# logic_board_Protorype_5_4_ver1.net
KiCad netlist of a schematic drawn in EAGLE
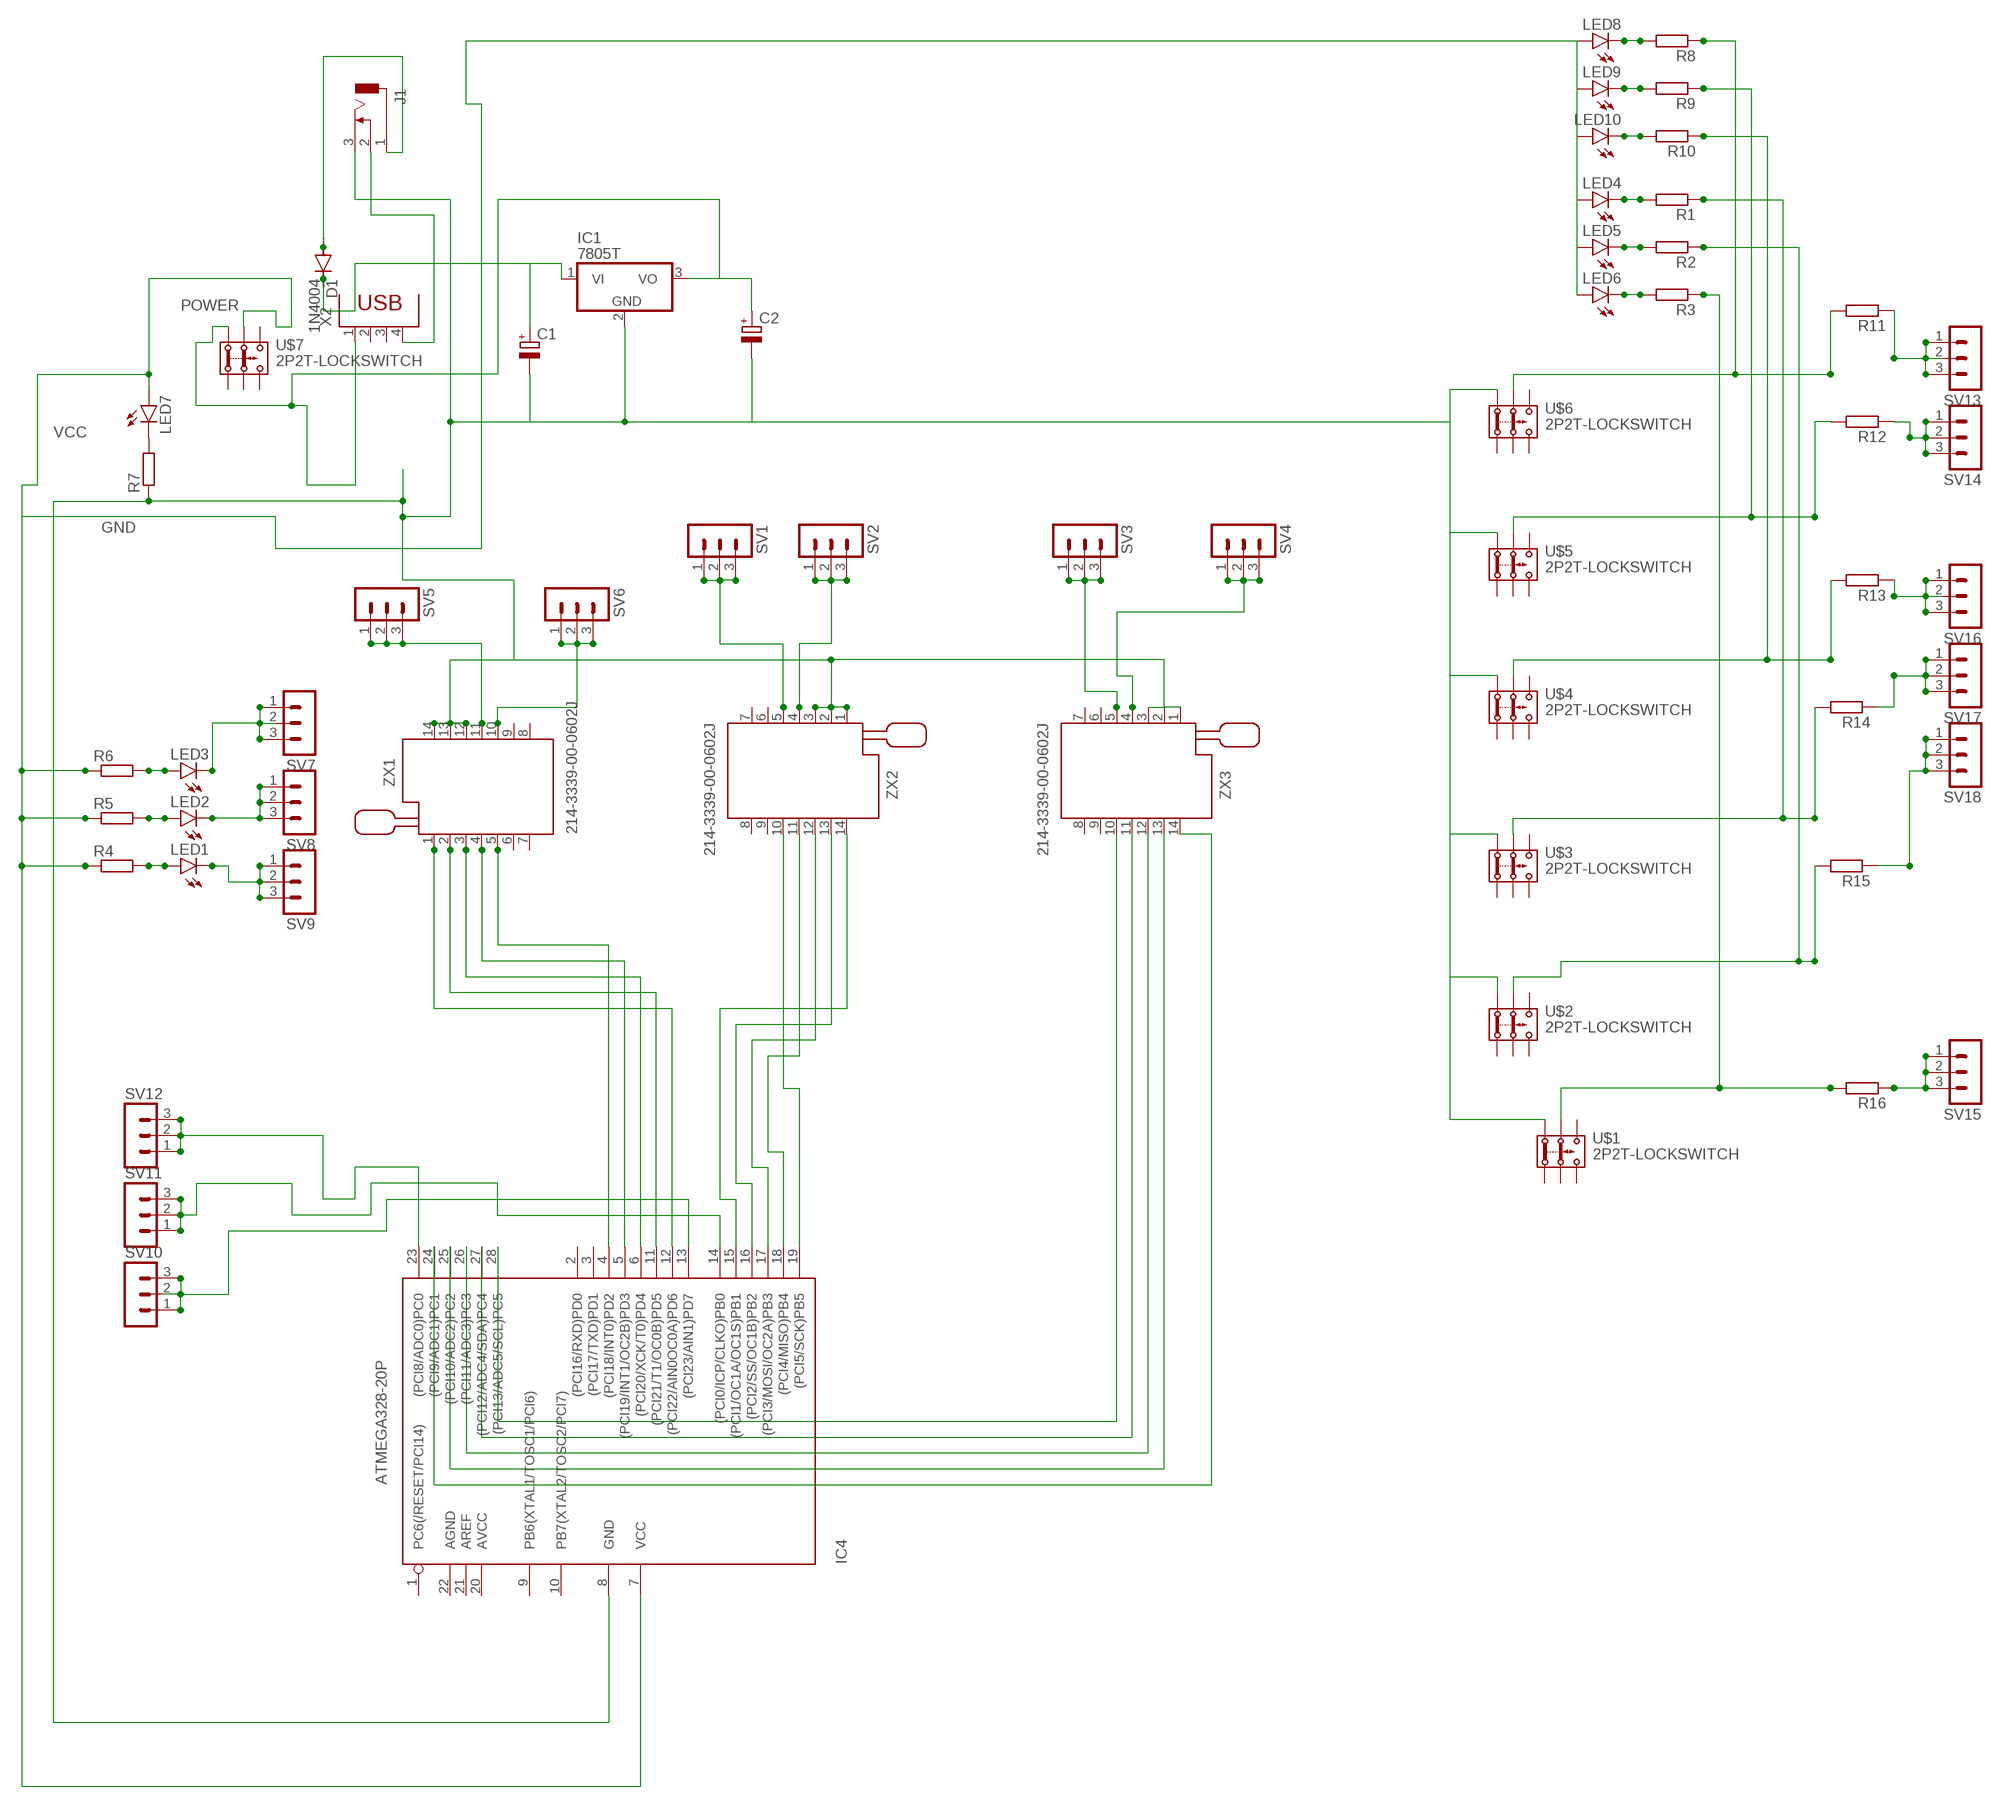
[diagram p0: schematic, sheet 1]

(export (version "E")
  (design (tool "Eeschema 10.0.6"))
  (components
    (comp (ref "C1")
      (value "CPOL-EUE2.5-6")
      (footprint "eagle-import:E2,5-6")
      (libsource (lib "eagle-import") (part "CPOL-EUE2.5-6"))
    )
    (comp (ref "C2")
      (value "CPOL-EUE2.5-6")
      (footprint "eagle-import:E2,5-6")
      (libsource (lib "eagle-import") (part "CPOL-EUE2.5-6"))
    )
    (comp (ref "D1")
      (value "1N4004")
      (footprint "eagle-import:DO41-10")
      (libsource (lib "eagle-import") (part "1N4004"))
    )
    (comp (ref "IC1")
      (value "7805T")
      (footprint "eagle-import:TO220H")
      (libsource (lib "eagle-import") (part "78T05"))
    )
    (comp (ref "IC4")
      (value "ATMEGA328-20P")
      (footprint "eagle-import:DIL28-3")
      (libsource (lib "eagle-import") (part "ATMEGA328P-20"))
    )
    (comp (ref "J1")
      (value "DCJ0303")
      (footprint "eagle-import:DCJ0303")
      (libsource (lib "eagle-import") (part "DCJ0303"))
    )
    (comp (ref "LED1")
      (value "LED5MM")
      (footprint "eagle-import:LED5MM")
      (libsource (lib "eagle-import") (part "LED5MM"))
    )
    (comp (ref "LED2")
      (value "LED5MM")
      (footprint "eagle-import:LED5MM")
      (libsource (lib "eagle-import") (part "LED5MM"))
    )
    (comp (ref "LED3")
      (value "LED5MM")
      (footprint "eagle-import:LED5MM")
      (libsource (lib "eagle-import") (part "LED5MM"))
    )
    (comp (ref "LED4")
      (value "LED5MM")
      (footprint "eagle-import:LED5MM")
      (libsource (lib "eagle-import") (part "LED5MM"))
    )
    (comp (ref "LED5")
      (value "LED5MM")
      (footprint "eagle-import:LED5MM")
      (libsource (lib "eagle-import") (part "LED5MM"))
    )
    (comp (ref "LED6")
      (value "LED5MM")
      (footprint "eagle-import:LED5MM")
      (libsource (lib "eagle-import") (part "LED5MM"))
    )
    (comp (ref "LED7")
      (value "LED5MM")
      (footprint "eagle-import:LED5MM")
      (libsource (lib "eagle-import") (part "LED5MM"))
    )
    (comp (ref "LED8")
      (value "LED5MM")
      (footprint "eagle-import:LED5MM")
      (libsource (lib "eagle-import") (part "LED5MM"))
    )
    (comp (ref "LED9")
      (value "LED5MM")
      (footprint "eagle-import:LED5MM")
      (libsource (lib "eagle-import") (part "LED5MM"))
    )
    (comp (ref "LED10")
      (value "LED5MM")
      (footprint "eagle-import:LED5MM")
      (libsource (lib "eagle-import") (part "LED5MM"))
    )
    (comp (ref "R1")
      (value "R-EU_0207/10")
      (footprint "eagle-import:0207_10")
      (libsource (lib "eagle-import") (part "R-EU_0207/10"))
    )
    (comp (ref "R2")
      (value "R-EU_0207/10")
      (footprint "eagle-import:0207_10")
      (libsource (lib "eagle-import") (part "R-EU_0207/10"))
    )
    (comp (ref "R3")
      (value "R-EU_0207/10")
      (footprint "eagle-import:0207_10")
      (libsource (lib "eagle-import") (part "R-EU_0207/10"))
    )
    (comp (ref "R4")
      (value "R-EU_0207/10")
      (footprint "eagle-import:0207_10")
      (libsource (lib "eagle-import") (part "R-EU_0207/10"))
    )
    (comp (ref "R5")
      (value "R-EU_0207/10")
      (footprint "eagle-import:0207_10")
      (libsource (lib "eagle-import") (part "R-EU_0207/10"))
    )
    (comp (ref "R6")
      (value "R-EU_0207/10")
      (footprint "eagle-import:0207_10")
      (libsource (lib "eagle-import") (part "R-EU_0207/10"))
    )
    (comp (ref "R7")
      (value "R-EU_0207/10")
      (footprint "eagle-import:0207_10")
      (libsource (lib "eagle-import") (part "R-EU_0207/10"))
    )
    (comp (ref "R8")
      (value "R-EU_0207/10")
      (footprint "eagle-import:0207_10")
      (libsource (lib "eagle-import") (part "R-EU_0207/10"))
    )
    (comp (ref "R9")
      (value "R-EU_0207/10")
      (footprint "eagle-import:0207_10")
      (libsource (lib "eagle-import") (part "R-EU_0207/10"))
    )
    (comp (ref "R10")
      (value "R-EU_0207/10")
      (footprint "eagle-import:0207_10")
      (libsource (lib "eagle-import") (part "R-EU_0207/10"))
    )
    (comp (ref "R11")
      (value "R-EU_0207/10")
      (footprint "eagle-import:0207_10")
      (libsource (lib "eagle-import") (part "R-EU_0207/10"))
    )
    (comp (ref "R12")
      (value "R-EU_0207/10")
      (footprint "eagle-import:0207_10")
      (libsource (lib "eagle-import") (part "R-EU_0207/10"))
    )
    (comp (ref "R13")
      (value "R-EU_0207/10")
      (footprint "eagle-import:0207_10")
      (libsource (lib "eagle-import") (part "R-EU_0207/10"))
    )
    (comp (ref "R14")
      (value "R-EU_0207/10")
      (footprint "eagle-import:0207_10")
      (libsource (lib "eagle-import") (part "R-EU_0207/10"))
    )
    (comp (ref "R15")
      (value "R-EU_0207/10")
      (footprint "eagle-import:0207_10")
      (libsource (lib "eagle-import") (part "R-EU_0207/10"))
    )
    (comp (ref "R16")
      (value "R-EU_0207/10")
      (footprint "eagle-import:0207_10")
      (libsource (lib "eagle-import") (part "R-EU_0207/10"))
    )
    (comp (ref "SV1")
      (value "MA03-1")
      (footprint "eagle-import:MA03-1")
      (libsource (lib "eagle-import") (part "MA03-1"))
    )
    (comp (ref "SV2")
      (value "MA03-1")
      (footprint "eagle-import:MA03-1")
      (libsource (lib "eagle-import") (part "MA03-1"))
    )
    (comp (ref "SV3")
      (value "MA03-1")
      (footprint "eagle-import:MA03-1")
      (libsource (lib "eagle-import") (part "MA03-1"))
    )
    (comp (ref "SV4")
      (value "MA03-1")
      (footprint "eagle-import:MA03-1")
      (libsource (lib "eagle-import") (part "MA03-1"))
    )
    (comp (ref "SV5")
      (value "MA03-1")
      (footprint "eagle-import:MA03-1")
      (libsource (lib "eagle-import") (part "MA03-1"))
    )
    (comp (ref "SV6")
      (value "MA03-1")
      (footprint "eagle-import:MA03-1")
      (libsource (lib "eagle-import") (part "MA03-1"))
    )
    (comp (ref "SV7")
      (value "MA03-1")
      (footprint "eagle-import:MA03-1")
      (libsource (lib "eagle-import") (part "MA03-1"))
    )
    (comp (ref "SV8")
      (value "MA03-1")
      (footprint "eagle-import:MA03-1")
      (libsource (lib "eagle-import") (part "MA03-1"))
    )
    (comp (ref "SV9")
      (value "MA03-1")
      (footprint "eagle-import:MA03-1")
      (libsource (lib "eagle-import") (part "MA03-1"))
    )
    (comp (ref "SV10")
      (value "MA03-1")
      (footprint "eagle-import:MA03-1")
      (libsource (lib "eagle-import") (part "MA03-1"))
    )
    (comp (ref "SV11")
      (value "MA03-1")
      (footprint "eagle-import:MA03-1")
      (libsource (lib "eagle-import") (part "MA03-1"))
    )
    (comp (ref "SV12")
      (value "MA03-1")
      (footprint "eagle-import:MA03-1")
      (libsource (lib "eagle-import") (part "MA03-1"))
    )
    (comp (ref "SV13")
      (value "MA03-1")
      (footprint "eagle-import:MA03-1")
      (libsource (lib "eagle-import") (part "MA03-1"))
    )
    (comp (ref "SV14")
      (value "MA03-1")
      (footprint "eagle-import:MA03-1")
      (libsource (lib "eagle-import") (part "MA03-1"))
    )
    (comp (ref "SV15")
      (value "MA03-1")
      (footprint "eagle-import:MA03-1")
      (libsource (lib "eagle-import") (part "MA03-1"))
    )
    (comp (ref "SV16")
      (value "MA03-1")
      (footprint "eagle-import:MA03-1")
      (libsource (lib "eagle-import") (part "MA03-1"))
    )
    (comp (ref "SV17")
      (value "MA03-1")
      (footprint "eagle-import:MA03-1")
      (libsource (lib "eagle-import") (part "MA03-1"))
    )
    (comp (ref "SV18")
      (value "MA03-1")
      (footprint "eagle-import:MA03-1")
      (libsource (lib "eagle-import") (part "MA03-1"))
    )
    (comp (ref "U$1")
      (value "2P2T-LOCKSWITCH")
      (footprint "eagle-import:2P2T-LOCKSWITCH")
      (libsource (lib "eagle-import") (part "2P2T-LOCKSWITCH"))
    )
    (comp (ref "U$2")
      (value "2P2T-LOCKSWITCH")
      (footprint "eagle-import:2P2T-LOCKSWITCH")
      (libsource (lib "eagle-import") (part "2P2T-LOCKSWITCH"))
    )
    (comp (ref "U$3")
      (value "2P2T-LOCKSWITCH")
      (footprint "eagle-import:2P2T-LOCKSWITCH")
      (libsource (lib "eagle-import") (part "2P2T-LOCKSWITCH"))
    )
    (comp (ref "U$4")
      (value "2P2T-LOCKSWITCH")
      (footprint "eagle-import:2P2T-LOCKSWITCH")
      (libsource (lib "eagle-import") (part "2P2T-LOCKSWITCH"))
    )
    (comp (ref "U$5")
      (value "2P2T-LOCKSWITCH")
      (footprint "eagle-import:2P2T-LOCKSWITCH")
      (libsource (lib "eagle-import") (part "2P2T-LOCKSWITCH"))
    )
    (comp (ref "U$6")
      (value "2P2T-LOCKSWITCH")
      (footprint "eagle-import:2P2T-LOCKSWITCH")
      (libsource (lib "eagle-import") (part "2P2T-LOCKSWITCH"))
    )
    (comp (ref "U$7")
      (value "2P2T-LOCKSWITCH")
      (footprint "eagle-import:2P2T-LOCKSWITCH")
      (libsource (lib "eagle-import") (part "2P2T-LOCKSWITCH"))
    )
    (comp (ref "X2")
      (value "PN61729")
      (footprint "eagle-import:PN61729")
      (libsource (lib "eagle-import") (part "PN61729"))
    )
    (comp (ref "ZX1")
      (value "214-3339-00-0602J")
      (footprint "eagle-import:214-3339-00-0602J")
      (fields (field (name "MF") "3M"))
      (libsource (lib "eagle-import") (part "214-3339-00-0602J"))
    )
    (comp (ref "ZX2")
      (value "214-3339-00-0602J")
      (footprint "eagle-import:214-3339-00-0602J")
      (fields (field (name "MF") "3M"))
      (libsource (lib "eagle-import") (part "214-3339-00-0602J"))
    )
    (comp (ref "ZX3")
      (value "214-3339-00-0602J")
      (footprint "eagle-import:214-3339-00-0602J")
      (fields (field (name "MF") "3M"))
      (libsource (lib "eagle-import") (part "214-3339-00-0602J"))
    )
  )
  (nets
    (net (code "1") (name "/GND") (class "Default")
      (node (ref "C1") (pin "-") (pinfunction "-_-") (pintype "passive"))
      (node (ref "C2") (pin "-") (pinfunction "-_-") (pintype "passive"))
      (node (ref "IC1") (pin "2") (pinfunction "GND_2") (pintype "passive"))
      (node (ref "IC4") (pin "8") (pinfunction "GND_8") (pintype "bidirectional"))
      (node (ref "J1") (pin "3") (pinfunction "3_3") (pintype "passive"))
      (node (ref "R7") (pin "1") (pinfunction "1_1") (pintype "passive"))
      (node (ref "U$1") (pin "1.1") (pinfunction "1.1_1.1") (pintype "passive"))
      (node (ref "U$2") (pin "1.1") (pinfunction "1.1_1.1") (pintype "passive"))
      (node (ref "U$3") (pin "1.1") (pinfunction "1.1_1.1") (pintype "passive"))
      (node (ref "U$4") (pin "1.1") (pinfunction "1.1_1.1") (pintype "passive"))
      (node (ref "U$5") (pin "1.1") (pinfunction "1.1_1.1") (pintype "passive"))
      (node (ref "U$6") (pin "1.1") (pinfunction "1.1_1.1") (pintype "passive"))
      (node (ref "ZX1") (pin "12") (pinfunction "12_12") (pintype "passive"))
      (node (ref "ZX1") (pin "13") (pinfunction "13_13") (pintype "passive"))
      (node (ref "ZX1") (pin "14") (pinfunction "14_14") (pintype "passive"))
      (node (ref "ZX2") (pin "1") (pinfunction "1_1") (pintype "passive"))
      (node (ref "ZX2") (pin "2") (pinfunction "2_2") (pintype "passive"))
      (node (ref "ZX2") (pin "3") (pinfunction "3_3") (pintype "passive"))
      (node (ref "ZX3") (pin "1") (pinfunction "1_1") (pintype "passive"))
      (node (ref "ZX3") (pin "2") (pinfunction "2_2") (pintype "passive"))
      (node (ref "ZX3") (pin "3") (pinfunction "3_3") (pintype "passive"))
    )
    (net (code "2") (name "/POWER") (class "Default")
      (node (ref "C2") (pin "+") (pinfunction "+_+") (pintype "passive"))
      (node (ref "IC1") (pin "3") (pinfunction "VO_3") (pintype "passive"))
      (node (ref "U$7") (pin "1.1") (pinfunction "1.1_1.1") (pintype "passive"))
      (node (ref "X2") (pin "1") (pinfunction "1_1") (pintype "passive"))
    )
    (net (code "3") (name "/VCC") (class "Default")
      (node (ref "IC4") (pin "7") (pinfunction "VCC_7") (pintype "bidirectional"))
      (node (ref "LED10") (pin "A") (pinfunction "A_A") (pintype "passive"))
      (node (ref "LED4") (pin "A") (pinfunction "A_A") (pintype "passive"))
      (node (ref "LED5") (pin "A") (pinfunction "A_A") (pintype "passive"))
      (node (ref "LED6") (pin "A") (pinfunction "A_A") (pintype "passive"))
      (node (ref "LED7") (pin "A") (pinfunction "A_A") (pintype "passive"))
      (node (ref "LED8") (pin "A") (pinfunction "A_A") (pintype "passive"))
      (node (ref "LED9") (pin "A") (pinfunction "A_A") (pintype "passive"))
      (node (ref "R4") (pin "1") (pinfunction "1_1") (pintype "passive"))
      (node (ref "R5") (pin "1") (pinfunction "1_1") (pintype "passive"))
      (node (ref "R6") (pin "1") (pinfunction "1_1") (pintype "passive"))
      (node (ref "U$7") (pin "2.1") (pinfunction "2.1_2.1") (pintype "passive"))
    )
    (net (code "4") (name "Net-(D1-PadA)") (class "Default")
      (node (ref "D1") (pin "A") (pinfunction "A_A") (pintype "passive"))
      (node (ref "J1") (pin "1") (pinfunction "1_1") (pintype "passive"))
    )
    (net (code "5") (name "Net-(IC1-VI)") (class "Default")
      (node (ref "C1") (pin "+") (pinfunction "+_+") (pintype "passive"))
      (node (ref "D1") (pin "C") (pinfunction "C_C") (pintype "passive"))
      (node (ref "IC1") (pin "1") (pinfunction "VI_1") (pintype "input"))
    )
    (net (code "6") (name "Net-(IC4-(PCI0{slash}ICP{slash}CLKO)PB0)") (class "Default")
      (node (ref "IC4") (pin "14") (pinfunction "(PCI0/ICP/CLKO)PB0_14") (pintype "bidirectional"))
      (node (ref "SV11") (pin "1") (pinfunction "1_1") (pintype "passive"))
      (node (ref "SV11") (pin "2") (pinfunction "2_2") (pintype "passive"))
      (node (ref "SV11") (pin "3") (pinfunction "3_3") (pintype "passive"))
    )
    (net (code "7") (name "Net-(IC4-(PCI1{slash}OC1A{slash}OC1S)PB1)") (class "Default")
      (node (ref "IC4") (pin "15") (pinfunction "(PCI1/OC1A/OC1S)PB1_15") (pintype "bidirectional"))
      (node (ref "ZX2") (pin "14") (pinfunction "14_14") (pintype "passive"))
    )
    (net (code "8") (name "Net-(IC4-(PCI2{slash}SS{slash}OC1B)PB2)") (class "Default")
      (node (ref "IC4") (pin "16") (pinfunction "(PCI2/SS/OC1B)PB2_16") (pintype "bidirectional"))
      (node (ref "ZX2") (pin "13") (pinfunction "13_13") (pintype "passive"))
    )
    (net (code "9") (name "Net-(IC4-(PCI3{slash}MOSI{slash}OC2A)PB3)") (class "Default")
      (node (ref "IC4") (pin "17") (pinfunction "(PCI3/MOSI/OC2A)PB3_17") (pintype "bidirectional"))
      (node (ref "ZX2") (pin "12") (pinfunction "12_12") (pintype "passive"))
    )
    (net (code "10") (name "Net-(IC4-(PCI4{slash}MISO)PB4)") (class "Default")
      (node (ref "IC4") (pin "18") (pinfunction "(PCI4/MISO)PB4_18") (pintype "bidirectional"))
      (node (ref "ZX2") (pin "11") (pinfunction "11_11") (pintype "passive"))
    )
    (net (code "11") (name "Net-(IC4-(PCI5{slash}SCK)PB5)") (class "Default")
      (node (ref "IC4") (pin "19") (pinfunction "(PCI5/SCK)PB5_19") (pintype "bidirectional"))
      (node (ref "ZX2") (pin "10") (pinfunction "10_10") (pintype "passive"))
    )
    (net (code "12") (name "Net-(IC4-(PCI8{slash}ADC0)PC0)") (class "Default")
      (node (ref "IC4") (pin "23") (pinfunction "(PCI8/ADC0)PC0_23") (pintype "bidirectional"))
      (node (ref "SV12") (pin "1") (pinfunction "1_1") (pintype "passive"))
      (node (ref "SV12") (pin "2") (pinfunction "2_2") (pintype "passive"))
      (node (ref "SV12") (pin "3") (pinfunction "3_3") (pintype "passive"))
    )
    (net (code "13") (name "Net-(IC4-(PCI9{slash}ADC1)PC1)") (class "Default")
      (node (ref "IC4") (pin "24") (pinfunction "(PCI9/ADC1)PC1_24") (pintype "bidirectional"))
      (node (ref "ZX3") (pin "14") (pinfunction "14_14") (pintype "passive"))
    )
    (net (code "14") (name "Net-(IC4-(PCI10{slash}ADC2)PC2)") (class "Default")
      (node (ref "IC4") (pin "25") (pinfunction "(PCI10/ADC2)PC2_25") (pintype "bidirectional"))
      (node (ref "ZX3") (pin "13") (pinfunction "13_13") (pintype "passive"))
    )
    (net (code "15") (name "Net-(IC4-(PCI11{slash}ADC3)PC3)") (class "Default")
      (node (ref "IC4") (pin "26") (pinfunction "(PCI11/ADC3)PC3_26") (pintype "bidirectional"))
      (node (ref "ZX3") (pin "12") (pinfunction "12_12") (pintype "passive"))
    )
    (net (code "16") (name "Net-(IC4-(PCI12{slash}ADC4{slash}SDA)PC4)") (class "Default")
      (node (ref "IC4") (pin "27") (pinfunction "(PCI12/ADC4/SDA)PC4_27") (pintype "bidirectional"))
      (node (ref "ZX3") (pin "11") (pinfunction "11_11") (pintype "passive"))
    )
    (net (code "17") (name "Net-(IC4-(PCI13{slash}ADC5{slash}SCL)PC5)") (class "Default")
      (node (ref "IC4") (pin "28") (pinfunction "(PCI13/ADC5/SCL)PC5_28") (pintype "bidirectional"))
      (node (ref "ZX3") (pin "10") (pinfunction "10_10") (pintype "passive"))
    )
    (net (code "18") (name "Net-(IC4-(PCI18{slash}INT0)PD2)") (class "Default")
      (node (ref "IC4") (pin "4") (pinfunction "(PCI18/INT0)PD2_4") (pintype "bidirectional"))
      (node (ref "ZX1") (pin "5") (pinfunction "5_5") (pintype "passive"))
    )
    (net (code "19") (name "Net-(IC4-(PCI19{slash}INT1{slash}OC2B)PD3)") (class "Default")
      (node (ref "IC4") (pin "5") (pinfunction "(PCI19/INT1/OC2B)PD3_5") (pintype "bidirectional"))
      (node (ref "ZX1") (pin "4") (pinfunction "4_4") (pintype "passive"))
    )
    (net (code "20") (name "Net-(IC4-(PCI20{slash}XCK{slash}T0)PD4)") (class "Default")
      (node (ref "IC4") (pin "6") (pinfunction "(PCI20/XCK/T0)PD4_6") (pintype "bidirectional"))
      (node (ref "ZX1") (pin "3") (pinfunction "3_3") (pintype "passive"))
    )
    (net (code "21") (name "Net-(IC4-(PCI21{slash}T1{slash}OC0B)PD5)") (class "Default")
      (node (ref "IC4") (pin "11") (pinfunction "(PCI21/T1/OC0B)PD5_11") (pintype "bidirectional"))
      (node (ref "ZX1") (pin "2") (pinfunction "2_2") (pintype "passive"))
    )
    (net (code "22") (name "Net-(IC4-(PCI22{slash}AIN0OC0A)PD6)") (class "Default")
      (node (ref "IC4") (pin "12") (pinfunction "(PCI22/AIN0OC0A)PD6_12") (pintype "bidirectional"))
      (node (ref "ZX1") (pin "1") (pinfunction "1_1") (pintype "passive"))
    )
    (net (code "23") (name "Net-(IC4-(PCI23{slash}AIN1)PD7)") (class "Default")
      (node (ref "IC4") (pin "13") (pinfunction "(PCI23/AIN1)PD7_13") (pintype "bidirectional"))
      (node (ref "SV10") (pin "1") (pinfunction "1_1") (pintype "passive"))
      (node (ref "SV10") (pin "2") (pinfunction "2_2") (pintype "passive"))
      (node (ref "SV10") (pin "3") (pinfunction "3_3") (pintype "passive"))
    )
    (net (code "24") (name "Net-(J1-Pad2)") (class "Default")
      (node (ref "J1") (pin "2") (pinfunction "2_2") (pintype "passive"))
      (node (ref "X2") (pin "4") (pinfunction "4_4") (pintype "passive"))
    )
    (net (code "25") (name "Net-(LED1-C)") (class "Default")
      (node (ref "LED1") (pin "K") (pinfunction "C_K") (pintype "passive"))
      (node (ref "SV9") (pin "1") (pinfunction "1_1") (pintype "passive"))
      (node (ref "SV9") (pin "2") (pinfunction "2_2") (pintype "passive"))
      (node (ref "SV9") (pin "3") (pinfunction "3_3") (pintype "passive"))
    )
    (net (code "26") (name "Net-(LED1-PadA)") (class "Default")
      (node (ref "LED1") (pin "A") (pinfunction "A_A") (pintype "passive"))
      (node (ref "R4") (pin "2") (pinfunction "2_2") (pintype "passive"))
    )
    (net (code "27") (name "Net-(LED2-C)") (class "Default")
      (node (ref "LED2") (pin "K") (pinfunction "C_K") (pintype "passive"))
      (node (ref "SV8") (pin "1") (pinfunction "1_1") (pintype "passive"))
      (node (ref "SV8") (pin "2") (pinfunction "2_2") (pintype "passive"))
      (node (ref "SV8") (pin "3") (pinfunction "3_3") (pintype "passive"))
    )
    (net (code "28") (name "Net-(LED2-PadA)") (class "Default")
      (node (ref "LED2") (pin "A") (pinfunction "A_A") (pintype "passive"))
      (node (ref "R5") (pin "2") (pinfunction "2_2") (pintype "passive"))
    )
    (net (code "29") (name "Net-(LED3-C)") (class "Default")
      (node (ref "LED3") (pin "K") (pinfunction "C_K") (pintype "passive"))
      (node (ref "SV7") (pin "1") (pinfunction "1_1") (pintype "passive"))
      (node (ref "SV7") (pin "2") (pinfunction "2_2") (pintype "passive"))
      (node (ref "SV7") (pin "3") (pinfunction "3_3") (pintype "passive"))
    )
    (net (code "30") (name "Net-(LED3-PadA)") (class "Default")
      (node (ref "LED3") (pin "A") (pinfunction "A_A") (pintype "passive"))
      (node (ref "R6") (pin "2") (pinfunction "2_2") (pintype "passive"))
    )
    (net (code "31") (name "Net-(LED4-C)") (class "Default")
      (node (ref "LED4") (pin "K") (pinfunction "C_K") (pintype "passive"))
      (node (ref "R1") (pin "2") (pinfunction "2_2") (pintype "passive"))
    )
    (net (code "32") (name "Net-(LED5-C)") (class "Default")
      (node (ref "LED5") (pin "K") (pinfunction "C_K") (pintype "passive"))
      (node (ref "R2") (pin "2") (pinfunction "2_2") (pintype "passive"))
    )
    (net (code "33") (name "Net-(LED6-C)") (class "Default")
      (node (ref "LED6") (pin "K") (pinfunction "C_K") (pintype "passive"))
      (node (ref "R3") (pin "2") (pinfunction "2_2") (pintype "passive"))
    )
    (net (code "34") (name "Net-(LED7-C)") (class "Default")
      (node (ref "LED7") (pin "K") (pinfunction "C_K") (pintype "passive"))
      (node (ref "R7") (pin "2") (pinfunction "2_2") (pintype "passive"))
    )
    (net (code "35") (name "Net-(LED8-C)") (class "Default")
      (node (ref "LED8") (pin "K") (pinfunction "C_K") (pintype "passive"))
      (node (ref "R8") (pin "2") (pinfunction "2_2") (pintype "passive"))
    )
    (net (code "36") (name "Net-(LED9-C)") (class "Default")
      (node (ref "LED9") (pin "K") (pinfunction "C_K") (pintype "passive"))
      (node (ref "R9") (pin "2") (pinfunction "2_2") (pintype "passive"))
    )
    (net (code "37") (name "Net-(LED10-C)") (class "Default")
      (node (ref "LED10") (pin "K") (pinfunction "C_K") (pintype "passive"))
      (node (ref "R10") (pin "2") (pinfunction "2_2") (pintype "passive"))
    )
    (net (code "38") (name "Net-(R1-Pad1)") (class "Default")
      (node (ref "R1") (pin "1") (pinfunction "1_1") (pintype "passive"))
      (node (ref "R14") (pin "2") (pinfunction "2_2") (pintype "passive"))
      (node (ref "U$3") (pin "2.1") (pinfunction "2.1_2.1") (pintype "passive"))
    )
    (net (code "39") (name "Net-(R10-Pad1)") (class "Default")
      (node (ref "R10") (pin "1") (pinfunction "1_1") (pintype "passive"))
      (node (ref "R13") (pin "2") (pinfunction "2_2") (pintype "passive"))
      (node (ref "U$4") (pin "2.1") (pinfunction "2.1_2.1") (pintype "passive"))
    )
    (net (code "40") (name "Net-(R11-Pad1)") (class "Default")
      (node (ref "R11") (pin "1") (pinfunction "1_1") (pintype "passive"))
      (node (ref "SV13") (pin "1") (pinfunction "1_1") (pintype "passive"))
      (node (ref "SV13") (pin "2") (pinfunction "2_2") (pintype "passive"))
      (node (ref "SV13") (pin "3") (pinfunction "3_3") (pintype "passive"))
    )
    (net (code "41") (name "Net-(R11-Pad2)") (class "Default")
      (node (ref "R11") (pin "2") (pinfunction "2_2") (pintype "passive"))
      (node (ref "R8") (pin "1") (pinfunction "1_1") (pintype "passive"))
      (node (ref "U$6") (pin "2.1") (pinfunction "2.1_2.1") (pintype "passive"))
    )
    (net (code "42") (name "Net-(R12-Pad1)") (class "Default")
      (node (ref "R12") (pin "1") (pinfunction "1_1") (pintype "passive"))
      (node (ref "SV14") (pin "1") (pinfunction "1_1") (pintype "passive"))
      (node (ref "SV14") (pin "2") (pinfunction "2_2") (pintype "passive"))
      (node (ref "SV14") (pin "3") (pinfunction "3_3") (pintype "passive"))
    )
    (net (code "43") (name "Net-(R12-Pad2)") (class "Default")
      (node (ref "R12") (pin "2") (pinfunction "2_2") (pintype "passive"))
      (node (ref "R9") (pin "1") (pinfunction "1_1") (pintype "passive"))
      (node (ref "U$5") (pin "2.1") (pinfunction "2.1_2.1") (pintype "passive"))
    )
    (net (code "44") (name "Net-(R13-Pad1)") (class "Default")
      (node (ref "R13") (pin "1") (pinfunction "1_1") (pintype "passive"))
      (node (ref "SV16") (pin "1") (pinfunction "1_1") (pintype "passive"))
      (node (ref "SV16") (pin "2") (pinfunction "2_2") (pintype "passive"))
      (node (ref "SV16") (pin "3") (pinfunction "3_3") (pintype "passive"))
    )
    (net (code "45") (name "Net-(R14-Pad1)") (class "Default")
      (node (ref "R14") (pin "1") (pinfunction "1_1") (pintype "passive"))
      (node (ref "SV17") (pin "1") (pinfunction "1_1") (pintype "passive"))
      (node (ref "SV17") (pin "2") (pinfunction "2_2") (pintype "passive"))
      (node (ref "SV17") (pin "3") (pinfunction "3_3") (pintype "passive"))
    )
    (net (code "46") (name "Net-(R15-Pad1)") (class "Default")
      (node (ref "R15") (pin "1") (pinfunction "1_1") (pintype "passive"))
      (node (ref "SV18") (pin "1") (pinfunction "1_1") (pintype "passive"))
      (node (ref "SV18") (pin "2") (pinfunction "2_2") (pintype "passive"))
      (node (ref "SV18") (pin "3") (pinfunction "3_3") (pintype "passive"))
    )
    (net (code "47") (name "Net-(R15-Pad2)") (class "Default")
      (node (ref "R15") (pin "2") (pinfunction "2_2") (pintype "passive"))
      (node (ref "R2") (pin "1") (pinfunction "1_1") (pintype "passive"))
      (node (ref "U$2") (pin "2.1") (pinfunction "2.1_2.1") (pintype "passive"))
    )
    (net (code "48") (name "Net-(R16-Pad1)") (class "Default")
      (node (ref "R16") (pin "1") (pinfunction "1_1") (pintype "passive"))
      (node (ref "SV15") (pin "1") (pinfunction "1_1") (pintype "passive"))
      (node (ref "SV15") (pin "2") (pinfunction "2_2") (pintype "passive"))
      (node (ref "SV15") (pin "3") (pinfunction "3_3") (pintype "passive"))
    )
    (net (code "49") (name "Net-(R16-Pad2)") (class "Default")
      (node (ref "R16") (pin "2") (pinfunction "2_2") (pintype "passive"))
      (node (ref "R3") (pin "1") (pinfunction "1_1") (pintype "passive"))
      (node (ref "U$1") (pin "2.1") (pinfunction "2.1_2.1") (pintype "passive"))
    )
    (net (code "50") (name "Net-(SV1-Pad1)") (class "Default")
      (node (ref "SV1") (pin "1") (pinfunction "1_1") (pintype "passive"))
      (node (ref "SV1") (pin "2") (pinfunction "2_2") (pintype "passive"))
      (node (ref "SV1") (pin "3") (pinfunction "3_3") (pintype "passive"))
      (node (ref "ZX2") (pin "5") (pinfunction "5_5") (pintype "passive"))
    )
    (net (code "51") (name "Net-(SV2-Pad1)") (class "Default")
      (node (ref "SV2") (pin "1") (pinfunction "1_1") (pintype "passive"))
      (node (ref "SV2") (pin "2") (pinfunction "2_2") (pintype "passive"))
      (node (ref "SV2") (pin "3") (pinfunction "3_3") (pintype "passive"))
      (node (ref "ZX2") (pin "4") (pinfunction "4_4") (pintype "passive"))
    )
    (net (code "52") (name "Net-(SV3-Pad1)") (class "Default")
      (node (ref "SV3") (pin "1") (pinfunction "1_1") (pintype "passive"))
      (node (ref "SV3") (pin "2") (pinfunction "2_2") (pintype "passive"))
      (node (ref "SV3") (pin "3") (pinfunction "3_3") (pintype "passive"))
      (node (ref "ZX3") (pin "5") (pinfunction "5_5") (pintype "passive"))
    )
    (net (code "53") (name "Net-(SV4-Pad1)") (class "Default")
      (node (ref "SV4") (pin "1") (pinfunction "1_1") (pintype "passive"))
      (node (ref "SV4") (pin "2") (pinfunction "2_2") (pintype "passive"))
      (node (ref "SV4") (pin "3") (pinfunction "3_3") (pintype "passive"))
      (node (ref "ZX3") (pin "4") (pinfunction "4_4") (pintype "passive"))
    )
    (net (code "54") (name "Net-(SV5-Pad1)") (class "Default")
      (node (ref "SV5") (pin "1") (pinfunction "1_1") (pintype "passive"))
      (node (ref "SV5") (pin "2") (pinfunction "2_2") (pintype "passive"))
      (node (ref "SV5") (pin "3") (pinfunction "3_3") (pintype "passive"))
      (node (ref "ZX1") (pin "11") (pinfunction "11_11") (pintype "passive"))
    )
    (net (code "55") (name "Net-(SV6-Pad1)") (class "Default")
      (node (ref "SV6") (pin "1") (pinfunction "1_1") (pintype "passive"))
      (node (ref "SV6") (pin "2") (pinfunction "2_2") (pintype "passive"))
      (node (ref "SV6") (pin "3") (pinfunction "3_3") (pintype "passive"))
      (node (ref "ZX1") (pin "10") (pinfunction "10_10") (pintype "passive"))
    )
    (net (code "56") (name "unconnected-(IC4-(PCI16{slash}RXD)PD0-Pad2)") (class "Default")
      (node (ref "IC4") (pin "2") (pinfunction "(PCI16/RXD)PD0_2") (pintype "bidirectional"))
    )
    (net (code "57") (name "unconnected-(IC4-(PCI17{slash}TXD)PD1-Pad3)") (class "Default")
      (node (ref "IC4") (pin "3") (pinfunction "(PCI17/TXD)PD1_3") (pintype "bidirectional"))
    )
    (net (code "58") (name "unconnected-(IC4-AGND-Pad22)") (class "Default")
      (node (ref "IC4") (pin "22") (pinfunction "AGND_22") (pintype "bidirectional"))
    )
    (net (code "59") (name "unconnected-(IC4-AREF-Pad21)") (class "Default")
      (node (ref "IC4") (pin "21") (pinfunction "AREF_21") (pintype "bidirectional"))
    )
    (net (code "60") (name "unconnected-(IC4-AVCC-Pad20)") (class "Default")
      (node (ref "IC4") (pin "20") (pinfunction "AVCC_20") (pintype "bidirectional"))
    )
    (net (code "61") (name "unconnected-(IC4-PB6(XTAL1{slash}TOSC1{slash}PCI6)-Pad9)") (class "Default")
      (node (ref "IC4") (pin "9") (pinfunction "PB6(XTAL1/TOSC1/PCI6)_9") (pintype "bidirectional"))
    )
    (net (code "62") (name "unconnected-(IC4-PB7(XTAL2{slash}TOSC2{slash}PCI7)-Pad10)") (class "Default")
      (node (ref "IC4") (pin "10") (pinfunction "PB7(XTAL2/TOSC2/PCI7)_10") (pintype "bidirectional"))
    )
    (net (code "63") (name "unconnected-(IC4-PC6({slash}RESET{slash}PCI14)-Pad1)") (class "Default")
      (node (ref "IC4") (pin "1") (pinfunction "PC6(/RESET/PCI14)_1") (pintype "bidirectional"))
    )
    (net (code "64") (name "unconnected-(U$1-Pad1.2)") (class "Default")
      (node (ref "U$1") (pin "1.2") (pinfunction "1.2_1.2") (pintype "passive"))
    )
    (net (code "65") (name "unconnected-(U$1-Pad2.2)") (class "Default")
      (node (ref "U$1") (pin "2.2") (pinfunction "2.2_2.2") (pintype "passive"))
    )
    (net (code "66") (name "unconnected-(U$1-Pad3.1)") (class "Default")
      (node (ref "U$1") (pin "3.1") (pinfunction "3.1_3.1") (pintype "passive"))
    )
    (net (code "67") (name "unconnected-(U$1-Pad3.2)") (class "Default")
      (node (ref "U$1") (pin "3.2") (pinfunction "3.2_3.2") (pintype "passive"))
    )
    (net (code "68") (name "unconnected-(U$2-Pad1.2)") (class "Default")
      (node (ref "U$2") (pin "1.2") (pinfunction "1.2_1.2") (pintype "passive"))
    )
    (net (code "69") (name "unconnected-(U$2-Pad2.2)") (class "Default")
      (node (ref "U$2") (pin "2.2") (pinfunction "2.2_2.2") (pintype "passive"))
    )
    (net (code "70") (name "unconnected-(U$2-Pad3.1)") (class "Default")
      (node (ref "U$2") (pin "3.1") (pinfunction "3.1_3.1") (pintype "passive"))
    )
    (net (code "71") (name "unconnected-(U$2-Pad3.2)") (class "Default")
      (node (ref "U$2") (pin "3.2") (pinfunction "3.2_3.2") (pintype "passive"))
    )
    (net (code "72") (name "unconnected-(U$3-Pad1.2)") (class "Default")
      (node (ref "U$3") (pin "1.2") (pinfunction "1.2_1.2") (pintype "passive"))
    )
    (net (code "73") (name "unconnected-(U$3-Pad2.2)") (class "Default")
      (node (ref "U$3") (pin "2.2") (pinfunction "2.2_2.2") (pintype "passive"))
    )
    (net (code "74") (name "unconnected-(U$3-Pad3.1)") (class "Default")
      (node (ref "U$3") (pin "3.1") (pinfunction "3.1_3.1") (pintype "passive"))
    )
    (net (code "75") (name "unconnected-(U$3-Pad3.2)") (class "Default")
      (node (ref "U$3") (pin "3.2") (pinfunction "3.2_3.2") (pintype "passive"))
    )
    (net (code "76") (name "unconnected-(U$4-Pad1.2)") (class "Default")
      (node (ref "U$4") (pin "1.2") (pinfunction "1.2_1.2") (pintype "passive"))
    )
    (net (code "77") (name "unconnected-(U$4-Pad2.2)") (class "Default")
      (node (ref "U$4") (pin "2.2") (pinfunction "2.2_2.2") (pintype "passive"))
    )
    (net (code "78") (name "unconnected-(U$4-Pad3.1)") (class "Default")
      (node (ref "U$4") (pin "3.1") (pinfunction "3.1_3.1") (pintype "passive"))
    )
    (net (code "79") (name "unconnected-(U$4-Pad3.2)") (class "Default")
      (node (ref "U$4") (pin "3.2") (pinfunction "3.2_3.2") (pintype "passive"))
    )
    (net (code "80") (name "unconnected-(U$5-Pad1.2)") (class "Default")
      (node (ref "U$5") (pin "1.2") (pinfunction "1.2_1.2") (pintype "passive"))
    )
    (net (code "81") (name "unconnected-(U$5-Pad2.2)") (class "Default")
      (node (ref "U$5") (pin "2.2") (pinfunction "2.2_2.2") (pintype "passive"))
    )
    (net (code "82") (name "unconnected-(U$5-Pad3.1)") (class "Default")
      (node (ref "U$5") (pin "3.1") (pinfunction "3.1_3.1") (pintype "passive"))
    )
    (net (code "83") (name "unconnected-(U$5-Pad3.2)") (class "Default")
      (node (ref "U$5") (pin "3.2") (pinfunction "3.2_3.2") (pintype "passive"))
    )
    (net (code "84") (name "unconnected-(U$6-Pad1.2)") (class "Default")
      (node (ref "U$6") (pin "1.2") (pinfunction "1.2_1.2") (pintype "passive"))
    )
    (net (code "85") (name "unconnected-(U$6-Pad2.2)") (class "Default")
      (node (ref "U$6") (pin "2.2") (pinfunction "2.2_2.2") (pintype "passive"))
    )
    (net (code "86") (name "unconnected-(U$6-Pad3.1)") (class "Default")
      (node (ref "U$6") (pin "3.1") (pinfunction "3.1_3.1") (pintype "passive"))
    )
    (net (code "87") (name "unconnected-(U$6-Pad3.2)") (class "Default")
      (node (ref "U$6") (pin "3.2") (pinfunction "3.2_3.2") (pintype "passive"))
    )
    (net (code "88") (name "unconnected-(U$7-Pad1.2)") (class "Default")
      (node (ref "U$7") (pin "1.2") (pinfunction "1.2_1.2") (pintype "passive"))
    )
    (net (code "89") (name "unconnected-(U$7-Pad2.2)") (class "Default")
      (node (ref "U$7") (pin "2.2") (pinfunction "2.2_2.2") (pintype "passive"))
    )
    (net (code "90") (name "unconnected-(U$7-Pad3.1)") (class "Default")
      (node (ref "U$7") (pin "3.1") (pinfunction "3.1_3.1") (pintype "passive"))
    )
    (net (code "91") (name "unconnected-(U$7-Pad3.2)") (class "Default")
      (node (ref "U$7") (pin "3.2") (pinfunction "3.2_3.2") (pintype "passive"))
    )
    (net (code "92") (name "unconnected-(X2-Pad2)") (class "Default")
      (node (ref "X2") (pin "2") (pinfunction "2_2") (pintype "passive"))
    )
    (net (code "93") (name "unconnected-(X2-Pad3)") (class "Default")
      (node (ref "X2") (pin "3") (pinfunction "3_3") (pintype "passive"))
    )
    (net (code "94") (name "unconnected-(ZX1-Pad6)") (class "Default")
      (node (ref "ZX1") (pin "6") (pinfunction "6_6") (pintype "passive"))
    )
    (net (code "95") (name "unconnected-(ZX1-Pad7)") (class "Default")
      (node (ref "ZX1") (pin "7") (pinfunction "7_7") (pintype "passive"))
    )
    (net (code "96") (name "unconnected-(ZX1-Pad8)") (class "Default")
      (node (ref "ZX1") (pin "8") (pinfunction "8_8") (pintype "passive"))
    )
    (net (code "97") (name "unconnected-(ZX1-Pad9)") (class "Default")
      (node (ref "ZX1") (pin "9") (pinfunction "9_9") (pintype "passive"))
    )
    (net (code "98") (name "unconnected-(ZX2-Pad6)") (class "Default")
      (node (ref "ZX2") (pin "6") (pinfunction "6_6") (pintype "passive"))
    )
    (net (code "99") (name "unconnected-(ZX2-Pad7)") (class "Default")
      (node (ref "ZX2") (pin "7") (pinfunction "7_7") (pintype "passive"))
    )
    (net (code "100") (name "unconnected-(ZX2-Pad8)") (class "Default")
      (node (ref "ZX2") (pin "8") (pinfunction "8_8") (pintype "passive"))
    )
    (net (code "101") (name "unconnected-(ZX2-Pad9)") (class "Default")
      (node (ref "ZX2") (pin "9") (pinfunction "9_9") (pintype "passive"))
    )
    (net (code "102") (name "unconnected-(ZX3-Pad6)") (class "Default")
      (node (ref "ZX3") (pin "6") (pinfunction "6_6") (pintype "passive"))
    )
    (net (code "103") (name "unconnected-(ZX3-Pad7)") (class "Default")
      (node (ref "ZX3") (pin "7") (pinfunction "7_7") (pintype "passive"))
    )
    (net (code "104") (name "unconnected-(ZX3-Pad8)") (class "Default")
      (node (ref "ZX3") (pin "8") (pinfunction "8_8") (pintype "passive"))
    )
    (net (code "105") (name "unconnected-(ZX3-Pad9)") (class "Default")
      (node (ref "ZX3") (pin "9") (pinfunction "9_9") (pintype "passive"))
    )
  )
)
